# arduino_sh.net
KiCad netlist of a schematic drawn in Altium Designer
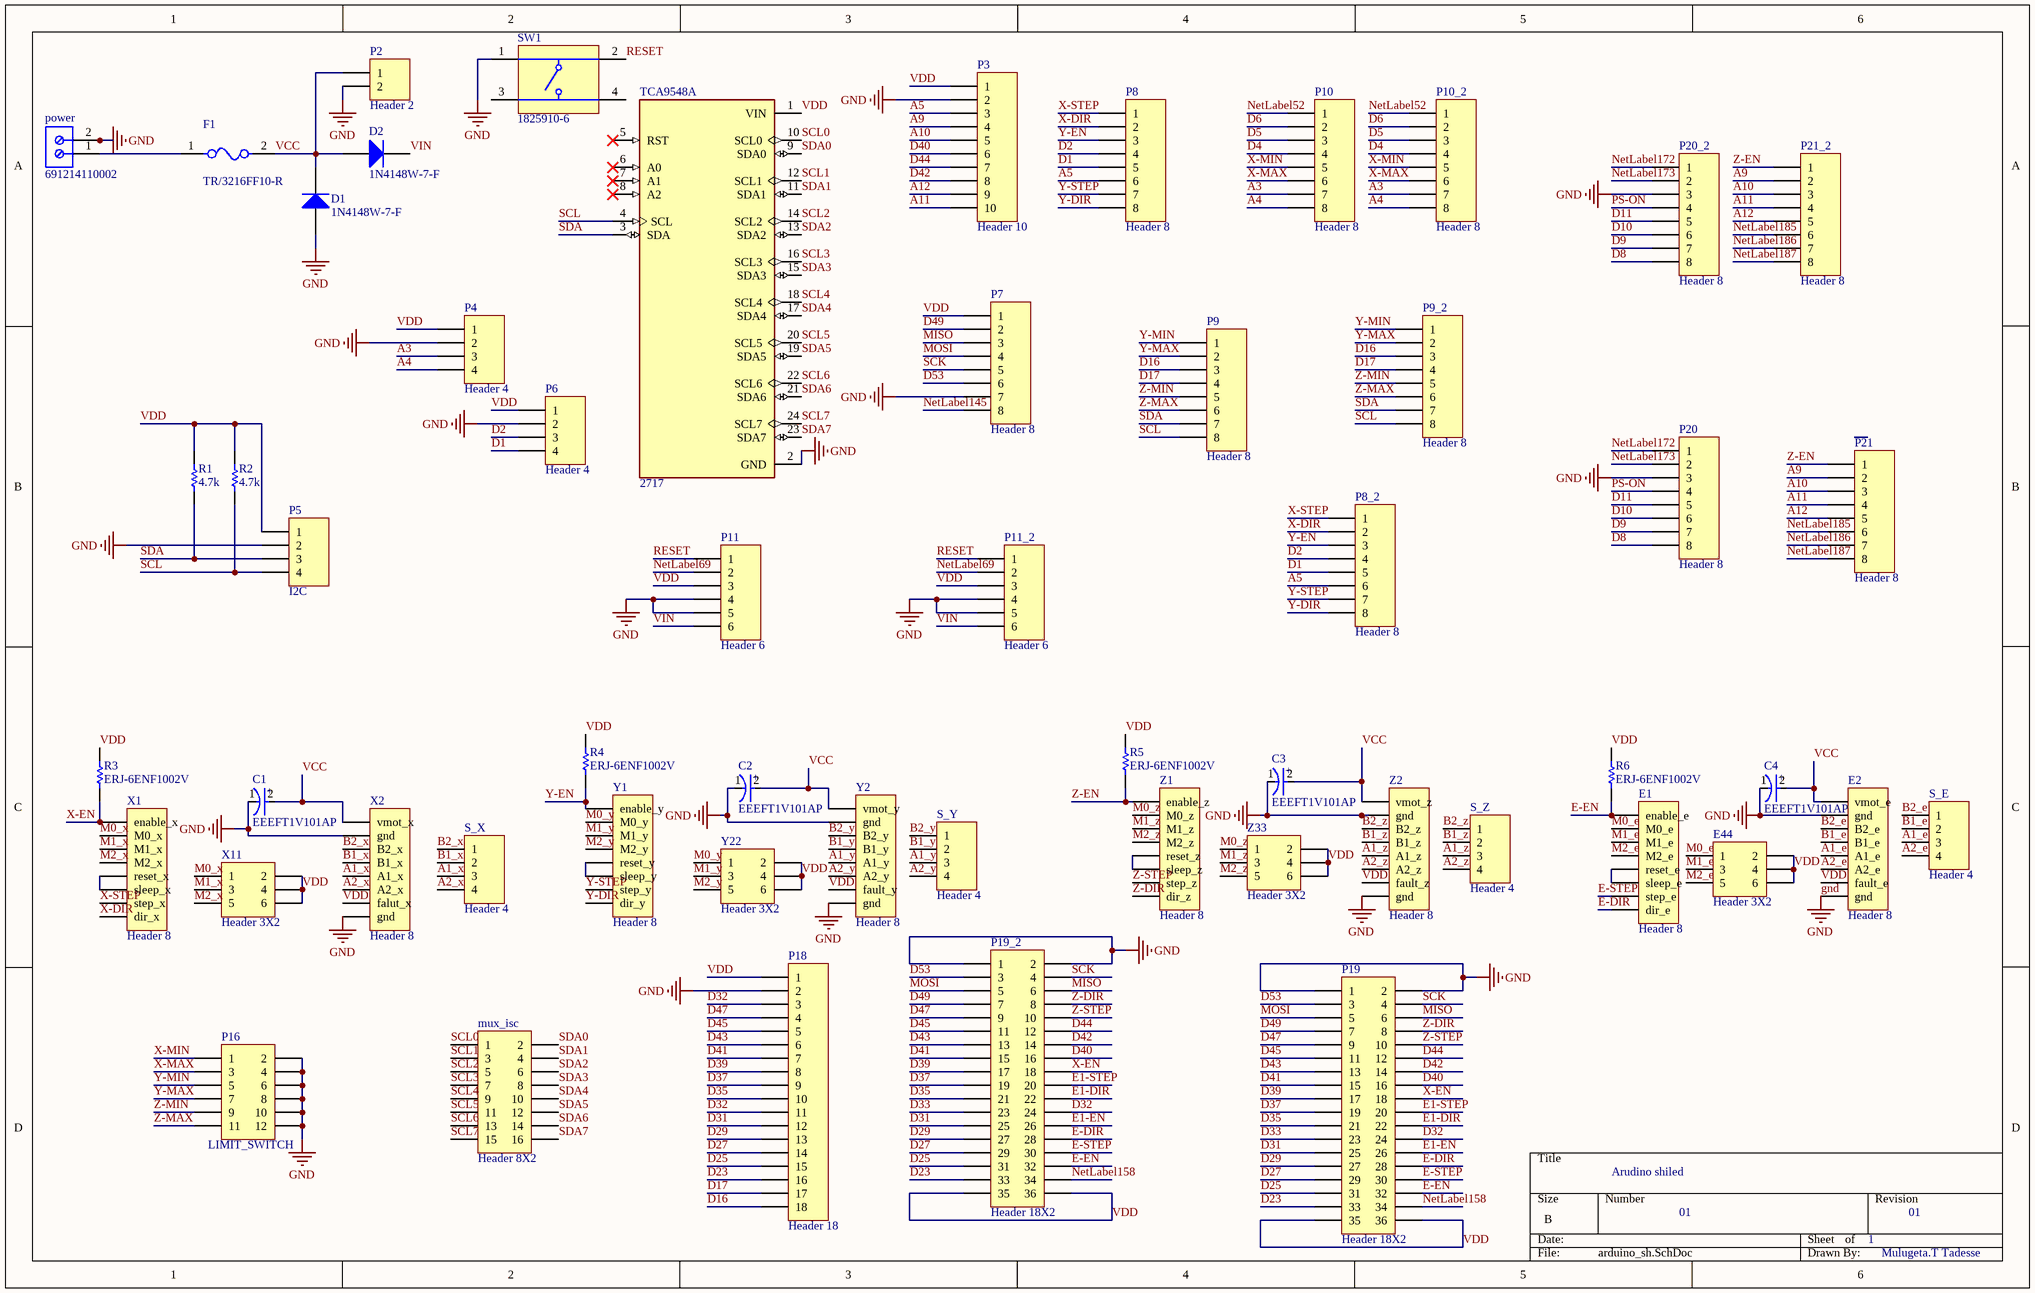
[diagram p0: arduino_sh.SchDoc]

(export (version "E")
  (design (tool "Eeschema 10.0.6"))
  (components
    (comp (ref "C1")
      (value "EEEFT1V101AP")
      (footprint "FP-FTD-MFG")
      (description "CAP ALUM 100UF 20% 35V SMD")
      (fields (field (name "VOLTAGE") "35V") (field (name "TOLERANCE") "20%"))
      (libsource (lib "Altium Content Vault") (part "a00bbbee19879c290e62620ae7e47b1"))
    )
    (comp (ref "C2")
      (value "EEEFT1V101AP")
      (footprint "FP-FTD-MFG")
      (description "CAP ALUM 100UF 20% 35V SMD")
      (fields (field (name "VOLTAGE") "35V") (field (name "TOLERANCE") "20%"))
      (libsource (lib "Altium Content Vault") (part "a00bbbee19879c290e62620ae7e47b1"))
    )
    (comp (ref "C3")
      (value "EEEFT1V101AP")
      (footprint "FP-FTD-MFG")
      (description "CAP ALUM 100UF 20% 35V SMD")
      (fields (field (name "VOLTAGE") "35V") (field (name "TOLERANCE") "20%"))
      (libsource (lib "Altium Content Vault") (part "a00bbbee19879c290e62620ae7e47b1"))
    )
    (comp (ref "C4")
      (value "EEEFT1V101AP")
      (footprint "FP-FTD-MFG")
      (description "CAP ALUM 100UF 20% 35V SMD")
      (fields (field (name "VOLTAGE") "35V") (field (name "TOLERANCE") "20%"))
      (libsource (lib "Altium Content Vault") (part "a00bbbee19879c290e62620ae7e47b1"))
    )
    (comp (ref "D1")
      (value "1N4148W-7-F")
      (footprint "DIOD-SOD123-2_V")
      (description "Fast Switching Diode, 100 V, 0.15 A, -65 to 150 degC, 2-Pin?SOD123, RoHS, Tape and Reel")
      (fields (field (name "MANUFACTURER") "DiodesIncorporated"))
      (libsource (lib "Altium Content Vault") (part "D-AK-2"))
    )
    (comp (ref "D2")
      (value "1N4148W-7-F")
      (footprint "DIOD-SOD123-2_V")
      (description "Fast Switching Diode, 100 V, 0.15 A, -65 to 150 degC, 2-Pin?SOD123, RoHS, Tape and Reel")
      (fields (field (name "MANUFACTURER") "DiodesIncorporated"))
      (libsource (lib "Altium Content Vault") (part "D-AK-2"))
    )
    (comp (ref "E1")
      (value "Header 8")
      (footprint "HDR1X8")
      (description "Header, 8-Pin")
      (fields (field (name "PUBLISHER") "Altium Limited"))
      (libsource (lib "Miscellaneous Connectors") (part "Header 8"))
    )
    (comp (ref "E2")
      (value "Header 8")
      (footprint "HDR1X8")
      (description "Header, 8-Pin")
      (fields (field (name "PUBLISHER") "Altium Limited"))
      (libsource (lib "Miscellaneous Connectors") (part "Header 8"))
    )
    (comp (ref "E44")
      (value "Header 3X2")
      (footprint "HDR2X3")
      (description "Header, 3-Pin, Dual row")
      (fields (field (name "PUBLISHER") "Altium Limited"))
      (libsource (lib "Miscellaneous Connectors") (part "Header 3X2"))
    )
    (comp (ref "F1")
      (value "TR/3216FF10-R")
      (footprint "FP-3216FF-MFG")
      (libsource (lib "Altium Content Vault") (part "5bcf9b9f640e542cf0359d10258e979"))
    )
    (comp (ref "mux_isc")
      (value "Header 8X2")
      (footprint "HDR2X8")
      (description "Header, 8-Pin, Dual row")
      (fields (field (name "PUBLISHER") "Altium Limited"))
      (libsource (lib "Miscellaneous Connectors") (part "Header 8X2"))
    )
    (comp (ref "P2")
      (value "Header 2")
      (footprint "HDR1X2")
      (description "Header, 2-Pin")
      (fields (field (name "PUBLISHER") "Altium Limited"))
      (libsource (lib "Miscellaneous Connectors") (part "Header 2"))
    )
    (comp (ref "P3")
      (value "Header 10")
      (footprint "HDR1X10")
      (description "Header, 10-Pin")
      (fields (field (name "PUBLISHER") "Altium Limited"))
      (libsource (lib "Miscellaneous Connectors") (part "Header 10"))
    )
    (comp (ref "P4")
      (value "Header 4")
      (footprint "HDR1X4")
      (description "Header, 4-Pin")
      (fields (field (name "PUBLISHER") "Altium Limited"))
      (libsource (lib "Miscellaneous Connectors") (part "Header 4"))
    )
    (comp (ref "P5")
      (value "I2C")
      (footprint "HDR1X4")
      (description "Header, 4-Pin")
      (fields (field (name "PUBLISHER") "Altium Limited"))
      (libsource (lib "Miscellaneous Connectors") (part "Header 4"))
    )
    (comp (ref "P6")
      (value "Header 4")
      (footprint "HDR1X4")
      (description "Header, 4-Pin")
      (fields (field (name "PUBLISHER") "Altium Limited"))
      (libsource (lib "Miscellaneous Connectors") (part "Header 4"))
    )
    (comp (ref "P7")
      (value "Header 8")
      (footprint "HDR1X8")
      (description "Header, 8-Pin")
      (fields (field (name "PUBLISHER") "Altium Limited"))
      (libsource (lib "Miscellaneous Connectors") (part "Header 8"))
    )
    (comp (ref "P8")
      (value "Header 8")
      (footprint "HDR1X8")
      (description "Header, 8-Pin")
      (fields (field (name "PUBLISHER") "Altium Limited"))
      (libsource (lib "Miscellaneous Connectors") (part "Header 8"))
    )
    (comp (ref "P8_2")
      (value "Header 8")
      (footprint "HDR1X8")
      (description "Header, 8-Pin")
      (fields (field (name "PUBLISHER") "Altium Limited"))
      (libsource (lib "Miscellaneous Connectors") (part "Header 8"))
    )
    (comp (ref "P9")
      (value "Header 8")
      (footprint "HDR1X8")
      (description "Header, 8-Pin")
      (fields (field (name "PUBLISHER") "Altium Limited"))
      (libsource (lib "Miscellaneous Connectors") (part "Header 8"))
    )
    (comp (ref "P9_2")
      (value "Header 8")
      (footprint "HDR1X8")
      (description "Header, 8-Pin")
      (fields (field (name "PUBLISHER") "Altium Limited"))
      (libsource (lib "Miscellaneous Connectors") (part "Header 8"))
    )
    (comp (ref "P10")
      (value "Header 8")
      (footprint "HDR1X8")
      (description "Header, 8-Pin")
      (fields (field (name "PUBLISHER") "Altium Limited"))
      (libsource (lib "Miscellaneous Connectors") (part "Header 8"))
    )
    (comp (ref "P10_2")
      (value "Header 8")
      (footprint "HDR1X8")
      (description "Header, 8-Pin")
      (fields (field (name "PUBLISHER") "Altium Limited"))
      (libsource (lib "Miscellaneous Connectors") (part "Header 8"))
    )
    (comp (ref "P11")
      (value "Header 6")
      (footprint "HDR1X6")
      (description "Header, 6-Pin")
      (fields (field (name "PUBLISHER") "Altium Limited"))
      (libsource (lib "Miscellaneous Connectors") (part "Header 6"))
    )
    (comp (ref "P11_2")
      (value "Header 6")
      (footprint "HDR1X6")
      (description "Header, 6-Pin")
      (fields (field (name "PUBLISHER") "Altium Limited"))
      (libsource (lib "Miscellaneous Connectors") (part "Header 6"))
    )
    (comp (ref "P16")
      (value "LIMIT_SWITCH")
      (footprint "HDR2X6")
      (description "Header, 6-Pin, Dual row")
      (fields (field (name "PUBLISHER") "Altium Limited"))
      (libsource (lib "Miscellaneous Connectors") (part "Header 6X2"))
    )
    (comp (ref "P18")
      (value "Header 18")
      (footprint "HDR1X18")
      (description "Header, 18-Pin")
      (fields (field (name "PUBLISHER") "Altium Limited"))
      (libsource (lib "Miscellaneous Connectors") (part "Header 18"))
    )
    (comp (ref "P19")
      (value "Header 18X2")
      (footprint "HDR2X18")
      (description "Header, 18-Pin, Dual row")
      (fields (field (name "PUBLISHER") "Altium Limited"))
      (libsource (lib "Miscellaneous Connectors") (part "Header 18X2"))
    )
    (comp (ref "P19_2")
      (value "Header 18X2")
      (footprint "HDR2X18")
      (description "Header, 18-Pin, Dual row")
      (fields (field (name "PUBLISHER") "Altium Limited"))
      (libsource (lib "Miscellaneous Connectors") (part "Header 18X2"))
    )
    (comp (ref "P20")
      (value "Header 8")
      (footprint "HDR1X8")
      (description "Header, 8-Pin")
      (fields (field (name "PUBLISHER") "Altium Limited"))
      (libsource (lib "Miscellaneous Connectors") (part "Header 8"))
    )
    (comp (ref "P20_2")
      (value "Header 8")
      (footprint "HDR1X8")
      (description "Header, 8-Pin")
      (fields (field (name "PUBLISHER") "Altium Limited"))
      (libsource (lib "Miscellaneous Connectors") (part "Header 8"))
    )
    (comp (ref "P21")
      (value "Header 8")
      (footprint "HDR1X8")
      (description "Header, 8-Pin")
      (fields (field (name "PUBLISHER") "Altium Limited"))
      (libsource (lib "Miscellaneous Connectors") (part "Header 8"))
    )
    (comp (ref "P21_2")
      (value "Header 8")
      (footprint "HDR1X8")
      (description "Header, 8-Pin")
      (fields (field (name "PUBLISHER") "Altium Limited"))
      (libsource (lib "Miscellaneous Connectors") (part "Header 8"))
    )
    (comp (ref "power")
      (value "691214110002")
      (footprint "691214110002")
      (fields (field (name "VOLTAGE") "300V"))
      (libsource (lib "Altium Content Vault") (part "TBL - 1R - 02P - Screw"))
    )
    (comp (ref "R1")
      (value "4.7k")
      (footprint "RESC2013X70X40ML20T20")
      (fields (field (name "MANUFACTURER") "Panasonic") (field (name "PART NUMBER") "ERJ-6ENF1002V"))
      (libsource (lib "Altium Content Vault") (part "RES"))
    )
    (comp (ref "R2")
      (value "4.7k")
      (footprint "RESC2013X70X40ML20T20")
      (fields (field (name "MANUFACTURER") "Panasonic") (field (name "PART NUMBER") "ERJ-6ENF1002V"))
      (libsource (lib "Altium Content Vault") (part "RES"))
    )
    (comp (ref "R3")
      (value "ERJ-6ENF1002V")
      (footprint "RESC2013X70X40ML20T20")
      (fields (field (name "MANUFACTURER") "Panasonic"))
      (libsource (lib "Altium Content Vault") (part "RES"))
    )
    (comp (ref "R4")
      (value "ERJ-6ENF1002V")
      (footprint "RESC2013X70X40ML20T20")
      (fields (field (name "MANUFACTURER") "Panasonic"))
      (libsource (lib "Altium Content Vault") (part "RES"))
    )
    (comp (ref "R5")
      (value "ERJ-6ENF1002V")
      (footprint "RESC2013X70X40ML20T20")
      (fields (field (name "MANUFACTURER") "Panasonic"))
      (libsource (lib "Altium Content Vault") (part "RES"))
    )
    (comp (ref "R6")
      (value "ERJ-6ENF1002V")
      (footprint "RESC2013X70X40ML20T20")
      (fields (field (name "MANUFACTURER") "Panasonic"))
      (libsource (lib "Altium Content Vault") (part "RES"))
    )
    (comp (ref "SW1")
      (value "1825910-6")
      (footprint "TECO-1825910-6_V")
      (description "Tact Switch, SPST-NO, 0.05 A, -35 to 85 degC, 4-Pin THD, RoHS, Bulk")
      (fields (field (name "MANUFACTURER") "TE Connectivity"))
      (libsource (lib "Altium Content Vault") (part "SW-SPST-4_A"))
    )
    (comp (ref "S_E")
      (value "Header 4")
      (footprint "HDR1X4")
      (description "Header, 4-Pin")
      (fields (field (name "PUBLISHER") "Altium Limited"))
      (libsource (lib "Miscellaneous Connectors") (part "Header 4"))
    )
    (comp (ref "S_X")
      (value "Header 4")
      (footprint "HDR1X4")
      (description "Header, 4-Pin")
      (fields (field (name "PUBLISHER") "Altium Limited"))
      (libsource (lib "Miscellaneous Connectors") (part "Header 4"))
    )
    (comp (ref "S_Y")
      (value "Header 4")
      (footprint "HDR1X4")
      (description "Header, 4-Pin")
      (fields (field (name "PUBLISHER") "Altium Limited"))
      (libsource (lib "Miscellaneous Connectors") (part "Header 4"))
    )
    (comp (ref "S_Z")
      (value "Header 4")
      (footprint "HDR1X4")
      (description "Header, 4-Pin")
      (fields (field (name "PUBLISHER") "Altium Limited"))
      (libsource (lib "Miscellaneous Connectors") (part "Header 4"))
    )
    (comp (ref "TCA9548A")
      (value "2717")
      (footprint "MODULE_2717")
      (description "Module: multiplexer; I2C interface multiplexer; TCA9548A; 3Ã·5VDC")
      (fields (field (name "MF") "Adafruit"))
      (libsource (lib "2717") (part "2717"))
    )
    (comp (ref "X1")
      (value "Header 8")
      (footprint "HDR1X8")
      (description "Header, 8-Pin")
      (fields (field (name "PUBLISHER") "Altium Limited"))
      (libsource (lib "Miscellaneous Connectors") (part "Header 8"))
    )
    (comp (ref "X2")
      (value "Header 8")
      (footprint "HDR1X8")
      (description "Header, 8-Pin")
      (fields (field (name "PUBLISHER") "Altium Limited"))
      (libsource (lib "Miscellaneous Connectors") (part "Header 8"))
    )
    (comp (ref "X11")
      (value "Header 3X2")
      (footprint "HDR2X3")
      (description "Header, 3-Pin, Dual row")
      (fields (field (name "PUBLISHER") "Altium Limited"))
      (libsource (lib "Miscellaneous Connectors") (part "Header 3X2"))
    )
    (comp (ref "Y1")
      (value "Header 8")
      (footprint "HDR1X8")
      (description "Header, 8-Pin")
      (fields (field (name "PUBLISHER") "Altium Limited"))
      (libsource (lib "Miscellaneous Connectors") (part "Header 8"))
    )
    (comp (ref "Y2")
      (value "Header 8")
      (footprint "HDR1X8")
      (description "Header, 8-Pin")
      (fields (field (name "PUBLISHER") "Altium Limited"))
      (libsource (lib "Miscellaneous Connectors") (part "Header 8"))
    )
    (comp (ref "Y22")
      (value "Header 3X2")
      (footprint "HDR2X3")
      (description "Header, 3-Pin, Dual row")
      (fields (field (name "PUBLISHER") "Altium Limited"))
      (libsource (lib "Miscellaneous Connectors") (part "Header 3X2"))
    )
    (comp (ref "Z1")
      (value "Header 8")
      (footprint "HDR1X8")
      (description "Header, 8-Pin")
      (fields (field (name "PUBLISHER") "Altium Limited"))
      (libsource (lib "Miscellaneous Connectors") (part "Header 8"))
    )
    (comp (ref "Z2")
      (value "Header 8")
      (footprint "HDR1X8")
      (description "Header, 8-Pin")
      (fields (field (name "PUBLISHER") "Altium Limited"))
      (libsource (lib "Miscellaneous Connectors") (part "Header 8"))
    )
    (comp (ref "Z33")
      (value "Header 3X2")
      (footprint "HDR2X3")
      (description "Header, 3-Pin, Dual row")
      (fields (field (name "PUBLISHER") "Altium Limited"))
      (libsource (lib "Miscellaneous Connectors") (part "Header 3X2"))
    )
  )
  (nets
    (net (code "1") (name "/A1_e") (class "Default")
      (node (ref "E2") (pin "5") (pinfunction "5_5") (pintype "passive"))
      (node (ref "S_E") (pin "3") (pinfunction "3_3") (pintype "passive"))
    )
    (net (code "2") (name "/A1_x") (class "Default")
      (node (ref "S_X") (pin "3") (pinfunction "3_3") (pintype "passive"))
      (node (ref "X2") (pin "5") (pinfunction "5_5") (pintype "passive"))
    )
    (net (code "3") (name "/A1_y") (class "Default")
      (node (ref "S_Y") (pin "3") (pinfunction "3_3") (pintype "passive"))
      (node (ref "Y2") (pin "5") (pinfunction "5_5") (pintype "passive"))
    )
    (net (code "4") (name "/A1_z") (class "Default")
      (node (ref "S_Z") (pin "3") (pinfunction "3_3") (pintype "passive"))
      (node (ref "Z2") (pin "5") (pinfunction "5_5") (pintype "passive"))
    )
    (net (code "5") (name "/A2_e") (class "Default")
      (node (ref "E2") (pin "6") (pinfunction "6_6") (pintype "passive"))
      (node (ref "S_E") (pin "4") (pinfunction "4_4") (pintype "passive"))
    )
    (net (code "6") (name "/A2_x") (class "Default")
      (node (ref "S_X") (pin "4") (pinfunction "4_4") (pintype "passive"))
      (node (ref "X2") (pin "6") (pinfunction "6_6") (pintype "passive"))
    )
    (net (code "7") (name "/A2_y") (class "Default")
      (node (ref "S_Y") (pin "4") (pinfunction "4_4") (pintype "passive"))
      (node (ref "Y2") (pin "6") (pinfunction "6_6") (pintype "passive"))
    )
    (net (code "8") (name "/A2_z") (class "Default")
      (node (ref "S_Z") (pin "4") (pinfunction "4_4") (pintype "passive"))
      (node (ref "Z2") (pin "6") (pinfunction "6_6") (pintype "passive"))
    )
    (net (code "9") (name "/A3") (class "Default")
      (node (ref "P10") (pin "7") (pinfunction "7_7") (pintype "passive"))
      (node (ref "P10_2") (pin "7") (pinfunction "7_7") (pintype "passive"))
      (node (ref "P4") (pin "3") (pinfunction "3_3") (pintype "passive"))
    )
    (net (code "10") (name "/A4") (class "Default")
      (node (ref "P10") (pin "8") (pinfunction "8_8") (pintype "passive"))
      (node (ref "P10_2") (pin "8") (pinfunction "8_8") (pintype "passive"))
      (node (ref "P4") (pin "4") (pinfunction "4_4") (pintype "passive"))
    )
    (net (code "11") (name "/A5") (class "Default")
      (node (ref "P3") (pin "3") (pinfunction "3_3") (pintype "passive"))
      (node (ref "P8") (pin "6") (pinfunction "6_6") (pintype "passive"))
      (node (ref "P8_2") (pin "6") (pinfunction "6_6") (pintype "passive"))
    )
    (net (code "12") (name "/A9") (class "Default")
      (node (ref "P21") (pin "2") (pinfunction "2_2") (pintype "passive"))
      (node (ref "P21_2") (pin "2") (pinfunction "2_2") (pintype "passive"))
      (node (ref "P3") (pin "4") (pinfunction "4_4") (pintype "passive"))
    )
    (net (code "13") (name "/A10") (class "Default")
      (node (ref "P21") (pin "3") (pinfunction "3_3") (pintype "passive"))
      (node (ref "P21_2") (pin "3") (pinfunction "3_3") (pintype "passive"))
      (node (ref "P3") (pin "5") (pinfunction "5_5") (pintype "passive"))
    )
    (net (code "14") (name "/A11") (class "Default")
      (node (ref "P21") (pin "4") (pinfunction "4_4") (pintype "passive"))
      (node (ref "P21_2") (pin "4") (pinfunction "4_4") (pintype "passive"))
      (node (ref "P3") (pin "10") (pinfunction "10_10") (pintype "passive"))
    )
    (net (code "15") (name "/A12") (class "Default")
      (node (ref "P21") (pin "5") (pinfunction "5_5") (pintype "passive"))
      (node (ref "P21_2") (pin "5") (pinfunction "5_5") (pintype "passive"))
      (node (ref "P3") (pin "9") (pinfunction "9_9") (pintype "passive"))
    )
    (net (code "16") (name "/B1_e") (class "Default")
      (node (ref "E2") (pin "4") (pinfunction "4_4") (pintype "passive"))
      (node (ref "S_E") (pin "2") (pinfunction "2_2") (pintype "passive"))
    )
    (net (code "17") (name "/B1_x") (class "Default")
      (node (ref "S_X") (pin "2") (pinfunction "2_2") (pintype "passive"))
      (node (ref "X2") (pin "4") (pinfunction "4_4") (pintype "passive"))
    )
    (net (code "18") (name "/B1_y") (class "Default")
      (node (ref "S_Y") (pin "2") (pinfunction "2_2") (pintype "passive"))
      (node (ref "Y2") (pin "4") (pinfunction "4_4") (pintype "passive"))
    )
    (net (code "19") (name "/B1_z") (class "Default")
      (node (ref "S_Z") (pin "2") (pinfunction "2_2") (pintype "passive"))
      (node (ref "Z2") (pin "4") (pinfunction "4_4") (pintype "passive"))
    )
    (net (code "20") (name "/B2_e") (class "Default")
      (node (ref "E2") (pin "3") (pinfunction "3_3") (pintype "passive"))
      (node (ref "S_E") (pin "1") (pinfunction "1_1") (pintype "passive"))
    )
    (net (code "21") (name "/B2_x") (class "Default")
      (node (ref "S_X") (pin "1") (pinfunction "1_1") (pintype "passive"))
      (node (ref "X2") (pin "3") (pinfunction "3_3") (pintype "passive"))
    )
    (net (code "22") (name "/B2_y") (class "Default")
      (node (ref "S_Y") (pin "1") (pinfunction "1_1") (pintype "passive"))
      (node (ref "Y2") (pin "3") (pinfunction "3_3") (pintype "passive"))
    )
    (net (code "23") (name "/B2_z") (class "Default")
      (node (ref "S_Z") (pin "1") (pinfunction "1_1") (pintype "passive"))
      (node (ref "Z2") (pin "3") (pinfunction "3_3") (pintype "passive"))
    )
    (net (code "24") (name "/D1") (class "Default")
      (node (ref "P6") (pin "4") (pinfunction "4_4") (pintype "passive"))
      (node (ref "P8") (pin "5") (pinfunction "5_5") (pintype "passive"))
      (node (ref "P8_2") (pin "5") (pinfunction "5_5") (pintype "passive"))
    )
    (net (code "25") (name "/D2") (class "Default")
      (node (ref "P6") (pin "3") (pinfunction "3_3") (pintype "passive"))
      (node (ref "P8") (pin "4") (pinfunction "4_4") (pintype "passive"))
      (node (ref "P8_2") (pin "4") (pinfunction "4_4") (pintype "passive"))
    )
    (net (code "26") (name "/D4") (class "Default")
      (node (ref "P10") (pin "4") (pinfunction "4_4") (pintype "passive"))
      (node (ref "P10_2") (pin "4") (pinfunction "4_4") (pintype "passive"))
    )
    (net (code "27") (name "/D5") (class "Default")
      (node (ref "P10") (pin "3") (pinfunction "3_3") (pintype "passive"))
      (node (ref "P10_2") (pin "3") (pinfunction "3_3") (pintype "passive"))
    )
    (net (code "28") (name "/D6") (class "Default")
      (node (ref "P10") (pin "2") (pinfunction "2_2") (pintype "passive"))
      (node (ref "P10_2") (pin "2") (pinfunction "2_2") (pintype "passive"))
    )
    (net (code "29") (name "/D8") (class "Default")
      (node (ref "P20") (pin "8") (pinfunction "8_8") (pintype "passive"))
      (node (ref "P20_2") (pin "8") (pinfunction "8_8") (pintype "passive"))
    )
    (net (code "30") (name "/D9") (class "Default")
      (node (ref "P20") (pin "7") (pinfunction "7_7") (pintype "passive"))
      (node (ref "P20_2") (pin "7") (pinfunction "7_7") (pintype "passive"))
    )
    (net (code "31") (name "/D10") (class "Default")
      (node (ref "P20") (pin "6") (pinfunction "6_6") (pintype "passive"))
      (node (ref "P20_2") (pin "6") (pinfunction "6_6") (pintype "passive"))
    )
    (net (code "32") (name "/D11") (class "Default")
      (node (ref "P20") (pin "5") (pinfunction "5_5") (pintype "passive"))
      (node (ref "P20_2") (pin "5") (pinfunction "5_5") (pintype "passive"))
    )
    (net (code "33") (name "/D16") (class "Default")
      (node (ref "P18") (pin "18") (pinfunction "18_18") (pintype "passive"))
      (node (ref "P9") (pin "3") (pinfunction "3_3") (pintype "passive"))
      (node (ref "P9_2") (pin "3") (pinfunction "3_3") (pintype "passive"))
    )
    (net (code "34") (name "/D17") (class "Default")
      (node (ref "P18") (pin "17") (pinfunction "17_17") (pintype "passive"))
      (node (ref "P9") (pin "4") (pinfunction "4_4") (pintype "passive"))
      (node (ref "P9_2") (pin "4") (pinfunction "4_4") (pintype "passive"))
    )
    (net (code "35") (name "/D23") (class "Default")
      (node (ref "P18") (pin "16") (pinfunction "16_16") (pintype "passive"))
      (node (ref "P19") (pin "33") (pinfunction "33_33") (pintype "passive"))
      (node (ref "P19_2") (pin "33") (pinfunction "33_33") (pintype "passive"))
    )
    (net (code "36") (name "/D25") (class "Default")
      (node (ref "P18") (pin "15") (pinfunction "15_15") (pintype "passive"))
      (node (ref "P19") (pin "31") (pinfunction "31_31") (pintype "passive"))
      (node (ref "P19_2") (pin "31") (pinfunction "31_31") (pintype "passive"))
    )
    (net (code "37") (name "/D27") (class "Default")
      (node (ref "P18") (pin "14") (pinfunction "14_14") (pintype "passive"))
      (node (ref "P19") (pin "29") (pinfunction "29_29") (pintype "passive"))
      (node (ref "P19_2") (pin "29") (pinfunction "29_29") (pintype "passive"))
    )
    (net (code "38") (name "/D29") (class "Default")
      (node (ref "P18") (pin "13") (pinfunction "13_13") (pintype "passive"))
      (node (ref "P19") (pin "27") (pinfunction "27_27") (pintype "passive"))
      (node (ref "P19_2") (pin "27") (pinfunction "27_27") (pintype "passive"))
    )
    (net (code "39") (name "/D31") (class "Default")
      (node (ref "P18") (pin "12") (pinfunction "12_12") (pintype "passive"))
      (node (ref "P19") (pin "25") (pinfunction "25_25") (pintype "passive"))
      (node (ref "P19_2") (pin "25") (pinfunction "25_25") (pintype "passive"))
    )
    (net (code "40") (name "/D32") (class "Default")
      (node (ref "P18") (pin "11") (pinfunction "11_11") (pintype "passive"))
      (node (ref "P18") (pin "3") (pinfunction "3_3") (pintype "passive"))
      (node (ref "P19") (pin "24") (pinfunction "24_24") (pintype "passive"))
      (node (ref "P19_2") (pin "24") (pinfunction "24_24") (pintype "passive"))
    )
    (net (code "41") (name "/D33") (class "Default")
      (node (ref "P19") (pin "23") (pinfunction "23_23") (pintype "passive"))
      (node (ref "P19_2") (pin "23") (pinfunction "23_23") (pintype "passive"))
    )
    (net (code "42") (name "/D35") (class "Default")
      (node (ref "P18") (pin "10") (pinfunction "10_10") (pintype "passive"))
      (node (ref "P19") (pin "21") (pinfunction "21_21") (pintype "passive"))
      (node (ref "P19_2") (pin "21") (pinfunction "21_21") (pintype "passive"))
    )
    (net (code "43") (name "/D37") (class "Default")
      (node (ref "P18") (pin "9") (pinfunction "9_9") (pintype "passive"))
      (node (ref "P19") (pin "19") (pinfunction "19_19") (pintype "passive"))
      (node (ref "P19_2") (pin "19") (pinfunction "19_19") (pintype "passive"))
    )
    (net (code "44") (name "/D39") (class "Default")
      (node (ref "P18") (pin "8") (pinfunction "8_8") (pintype "passive"))
      (node (ref "P19") (pin "17") (pinfunction "17_17") (pintype "passive"))
      (node (ref "P19_2") (pin "17") (pinfunction "17_17") (pintype "passive"))
    )
    (net (code "45") (name "/D40") (class "Default")
      (node (ref "P19") (pin "16") (pinfunction "16_16") (pintype "passive"))
      (node (ref "P19_2") (pin "16") (pinfunction "16_16") (pintype "passive"))
      (node (ref "P3") (pin "6") (pinfunction "6_6") (pintype "passive"))
    )
    (net (code "46") (name "/D41") (class "Default")
      (node (ref "P18") (pin "7") (pinfunction "7_7") (pintype "passive"))
      (node (ref "P19") (pin "15") (pinfunction "15_15") (pintype "passive"))
      (node (ref "P19_2") (pin "15") (pinfunction "15_15") (pintype "passive"))
    )
    (net (code "47") (name "/D42") (class "Default")
      (node (ref "P19") (pin "14") (pinfunction "14_14") (pintype "passive"))
      (node (ref "P19_2") (pin "14") (pinfunction "14_14") (pintype "passive"))
      (node (ref "P3") (pin "8") (pinfunction "8_8") (pintype "passive"))
    )
    (net (code "48") (name "/D43") (class "Default")
      (node (ref "P18") (pin "6") (pinfunction "6_6") (pintype "passive"))
      (node (ref "P19") (pin "13") (pinfunction "13_13") (pintype "passive"))
      (node (ref "P19_2") (pin "13") (pinfunction "13_13") (pintype "passive"))
    )
    (net (code "49") (name "/D44") (class "Default")
      (node (ref "P19") (pin "12") (pinfunction "12_12") (pintype "passive"))
      (node (ref "P19_2") (pin "12") (pinfunction "12_12") (pintype "passive"))
      (node (ref "P3") (pin "7") (pinfunction "7_7") (pintype "passive"))
    )
    (net (code "50") (name "/D45") (class "Default")
      (node (ref "P18") (pin "5") (pinfunction "5_5") (pintype "passive"))
      (node (ref "P19") (pin "11") (pinfunction "11_11") (pintype "passive"))
      (node (ref "P19_2") (pin "11") (pinfunction "11_11") (pintype "passive"))
    )
    (net (code "51") (name "/D47") (class "Default")
      (node (ref "P18") (pin "4") (pinfunction "4_4") (pintype "passive"))
      (node (ref "P19") (pin "9") (pinfunction "9_9") (pintype "passive"))
      (node (ref "P19_2") (pin "9") (pinfunction "9_9") (pintype "passive"))
    )
    (net (code "52") (name "/D49") (class "Default")
      (node (ref "P19") (pin "7") (pinfunction "7_7") (pintype "passive"))
      (node (ref "P19_2") (pin "7") (pinfunction "7_7") (pintype "passive"))
      (node (ref "P7") (pin "2") (pinfunction "2_2") (pintype "passive"))
    )
    (net (code "53") (name "/D53") (class "Default")
      (node (ref "P19") (pin "3") (pinfunction "3_3") (pintype "passive"))
      (node (ref "P19_2") (pin "3") (pinfunction "3_3") (pintype "passive"))
      (node (ref "P7") (pin "6") (pinfunction "6_6") (pintype "passive"))
    )
    (net (code "54") (name "/E-DIR") (class "Default")
      (node (ref "E1") (pin "8") (pinfunction "8_8") (pintype "passive"))
      (node (ref "P19") (pin "28") (pinfunction "28_28") (pintype "passive"))
      (node (ref "P19_2") (pin "28") (pinfunction "28_28") (pintype "passive"))
    )
    (net (code "55") (name "/E-EN") (class "Default")
      (node (ref "E1") (pin "1") (pinfunction "1_1") (pintype "passive"))
      (node (ref "P19") (pin "32") (pinfunction "32_32") (pintype "passive"))
      (node (ref "P19_2") (pin "32") (pinfunction "32_32") (pintype "passive"))
      (node (ref "R6") (pin "2") (pinfunction "2_2") (pintype "passive"))
    )
    (net (code "56") (name "/E-STEP") (class "Default")
      (node (ref "E1") (pin "7") (pinfunction "7_7") (pintype "passive"))
      (node (ref "P19") (pin "30") (pinfunction "30_30") (pintype "passive"))
      (node (ref "P19_2") (pin "30") (pinfunction "30_30") (pintype "passive"))
    )
    (net (code "57") (name "/E1-DIR") (class "Default")
      (node (ref "P19") (pin "22") (pinfunction "22_22") (pintype "passive"))
      (node (ref "P19_2") (pin "22") (pinfunction "22_22") (pintype "passive"))
    )
    (net (code "58") (name "/E1-EN") (class "Default")
      (node (ref "P19") (pin "26") (pinfunction "26_26") (pintype "passive"))
      (node (ref "P19_2") (pin "26") (pinfunction "26_26") (pintype "passive"))
    )
    (net (code "59") (name "/E1-STEP") (class "Default")
      (node (ref "P19") (pin "20") (pinfunction "20_20") (pintype "passive"))
      (node (ref "P19_2") (pin "20") (pinfunction "20_20") (pintype "passive"))
    )
    (net (code "60") (name "/M0_e") (class "Default")
      (node (ref "E1") (pin "2") (pinfunction "2_2") (pintype "passive"))
      (node (ref "E44") (pin "1") (pinfunction "1_1") (pintype "passive"))
    )
    (net (code "61") (name "/M0_x") (class "Default")
      (node (ref "X1") (pin "2") (pinfunction "2_2") (pintype "passive"))
      (node (ref "X11") (pin "1") (pinfunction "1_1") (pintype "passive"))
    )
    (net (code "62") (name "/M0_y") (class "Default")
      (node (ref "Y1") (pin "2") (pinfunction "2_2") (pintype "passive"))
      (node (ref "Y22") (pin "1") (pinfunction "1_1") (pintype "passive"))
    )
    (net (code "63") (name "/M0_z") (class "Default")
      (node (ref "Z1") (pin "2") (pinfunction "2_2") (pintype "passive"))
      (node (ref "Z33") (pin "1") (pinfunction "1_1") (pintype "passive"))
    )
    (net (code "64") (name "/M1_e") (class "Default")
      (node (ref "E1") (pin "3") (pinfunction "3_3") (pintype "passive"))
      (node (ref "E44") (pin "3") (pinfunction "3_3") (pintype "passive"))
    )
    (net (code "65") (name "/M1_x") (class "Default")
      (node (ref "X1") (pin "3") (pinfunction "3_3") (pintype "passive"))
      (node (ref "X11") (pin "3") (pinfunction "3_3") (pintype "passive"))
    )
    (net (code "66") (name "/M1_y") (class "Default")
      (node (ref "Y1") (pin "3") (pinfunction "3_3") (pintype "passive"))
      (node (ref "Y22") (pin "3") (pinfunction "3_3") (pintype "passive"))
    )
    (net (code "67") (name "/M1_z") (class "Default")
      (node (ref "Z1") (pin "3") (pinfunction "3_3") (pintype "passive"))
      (node (ref "Z33") (pin "3") (pinfunction "3_3") (pintype "passive"))
    )
    (net (code "68") (name "/M2_e") (class "Default")
      (node (ref "E1") (pin "4") (pinfunction "4_4") (pintype "passive"))
      (node (ref "E44") (pin "5") (pinfunction "5_5") (pintype "passive"))
    )
    (net (code "69") (name "/M2_x") (class "Default")
      (node (ref "X1") (pin "4") (pinfunction "4_4") (pintype "passive"))
      (node (ref "X11") (pin "5") (pinfunction "5_5") (pintype "passive"))
    )
    (net (code "70") (name "/M2_y") (class "Default")
      (node (ref "Y1") (pin "4") (pinfunction "4_4") (pintype "passive"))
      (node (ref "Y22") (pin "5") (pinfunction "5_5") (pintype "passive"))
    )
    (net (code "71") (name "/M2_z") (class "Default")
      (node (ref "Z1") (pin "4") (pinfunction "4_4") (pintype "passive"))
      (node (ref "Z33") (pin "5") (pinfunction "5_5") (pintype "passive"))
    )
    (net (code "72") (name "/MISO") (class "Default")
      (node (ref "P19") (pin "6") (pinfunction "6_6") (pintype "passive"))
      (node (ref "P19_2") (pin "6") (pinfunction "6_6") (pintype "passive"))
      (node (ref "P7") (pin "3") (pinfunction "3_3") (pintype "passive"))
    )
    (net (code "73") (name "/MOSI") (class "Default")
      (node (ref "P19") (pin "5") (pinfunction "5_5") (pintype "passive"))
      (node (ref "P19_2") (pin "5") (pinfunction "5_5") (pintype "passive"))
      (node (ref "P7") (pin "4") (pinfunction "4_4") (pintype "passive"))
    )
    (net (code "74") (name "/NetLabel52") (class "Default")
      (node (ref "P10") (pin "1") (pinfunction "1_1") (pintype "passive"))
      (node (ref "P10_2") (pin "1") (pinfunction "1_1") (pintype "passive"))
    )
    (net (code "75") (name "/NetLabel69") (class "Default")
      (node (ref "P11") (pin "2") (pinfunction "2_2") (pintype "passive"))
      (node (ref "P11_2") (pin "2") (pinfunction "2_2") (pintype "passive"))
    )
    (net (code "76") (name "/NetLabel145") (class "Default")
      (node (ref "P7") (pin "8") (pinfunction "8_8") (pintype "passive"))
    )
    (net (code "77") (name "/NetLabel158") (class "Default")
      (node (ref "P19") (pin "34") (pinfunction "34_34") (pintype "passive"))
      (node (ref "P19_2") (pin "34") (pinfunction "34_34") (pintype "passive"))
    )
    (net (code "78") (name "/NetLabel172") (class "Default")
      (node (ref "P20") (pin "1") (pinfunction "1_1") (pintype "passive"))
      (node (ref "P20_2") (pin "1") (pinfunction "1_1") (pintype "passive"))
    )
    (net (code "79") (name "/NetLabel173") (class "Default")
      (node (ref "P20") (pin "2") (pinfunction "2_2") (pintype "passive"))
      (node (ref "P20_2") (pin "2") (pinfunction "2_2") (pintype "passive"))
    )
    (net (code "80") (name "/NetLabel185") (class "Default")
      (node (ref "P21") (pin "6") (pinfunction "6_6") (pintype "passive"))
      (node (ref "P21_2") (pin "6") (pinfunction "6_6") (pintype "passive"))
    )
    (net (code "81") (name "/NetLabel186") (class "Default")
      (node (ref "P21") (pin "7") (pinfunction "7_7") (pintype "passive"))
      (node (ref "P21_2") (pin "7") (pinfunction "7_7") (pintype "passive"))
    )
    (net (code "82") (name "/NetLabel187") (class "Default")
      (node (ref "P21") (pin "8") (pinfunction "8_8") (pintype "passive"))
      (node (ref "P21_2") (pin "8") (pinfunction "8_8") (pintype "passive"))
    )
    (net (code "83") (name "/PS-ON") (class "Default")
      (node (ref "P20") (pin "4") (pinfunction "4_4") (pintype "passive"))
      (node (ref "P20_2") (pin "4") (pinfunction "4_4") (pintype "passive"))
    )
    (net (code "84") (name "/RESET") (class "Default")
      (node (ref "P11") (pin "1") (pinfunction "1_1") (pintype "passive"))
      (node (ref "P11_2") (pin "1") (pinfunction "1_1") (pintype "passive"))
      (node (ref "SW1") (pin "2") (pinfunction "2_2") (pintype "passive"))
    )
    (net (code "85") (name "/SCK") (class "Default")
      (node (ref "P19") (pin "4") (pinfunction "4_4") (pintype "passive"))
      (node (ref "P19_2") (pin "4") (pinfunction "4_4") (pintype "passive"))
      (node (ref "P7") (pin "5") (pinfunction "5_5") (pintype "passive"))
    )
    (net (code "86") (name "/SCL") (class "Default")
      (node (ref "P5") (pin "4") (pinfunction "4_4") (pintype "passive"))
      (node (ref "P9") (pin "8") (pinfunction "8_8") (pintype "passive"))
      (node (ref "P9_2") (pin "8") (pinfunction "8_8") (pintype "passive"))
      (node (ref "R2") (pin "2") (pinfunction "2_2") (pintype "passive"))
      (node (ref "TCA9548A") (pin "4") (pinfunction "SCL_4") (pintype "input"))
    )
    (net (code "87") (name "/SCL0") (class "Default")
      (node (ref "TCA9548A") (pin "10") (pinfunction "SCL0_10") (pintype "output"))
      (node (ref "mux_isc") (pin "1") (pinfunction "1_1") (pintype "passive"))
    )
    (net (code "88") (name "/SCL1") (class "Default")
      (node (ref "TCA9548A") (pin "12") (pinfunction "SCL1_12") (pintype "output"))
      (node (ref "mux_isc") (pin "3") (pinfunction "3_3") (pintype "passive"))
    )
    (net (code "89") (name "/SCL2") (class "Default")
      (node (ref "TCA9548A") (pin "14") (pinfunction "SCL2_14") (pintype "output"))
      (node (ref "mux_isc") (pin "5") (pinfunction "5_5") (pintype "passive"))
    )
    (net (code "90") (name "/SCL3") (class "Default")
      (node (ref "TCA9548A") (pin "16") (pinfunction "SCL3_16") (pintype "output"))
      (node (ref "mux_isc") (pin "7") (pinfunction "7_7") (pintype "passive"))
    )
    (net (code "91") (name "/SCL4") (class "Default")
      (node (ref "TCA9548A") (pin "18") (pinfunction "SCL4_18") (pintype "output"))
      (node (ref "mux_isc") (pin "9") (pinfunction "9_9") (pintype "passive"))
    )
    (net (code "92") (name "/SCL5") (class "Default")
      (node (ref "TCA9548A") (pin "20") (pinfunction "SCL5_20") (pintype "output"))
      (node (ref "mux_isc") (pin "11") (pinfunction "11_11") (pintype "passive"))
    )
    (net (code "93") (name "/SCL6") (class "Default")
      (node (ref "TCA9548A") (pin "22") (pinfunction "SCL6_22") (pintype "output"))
      (node (ref "mux_isc") (pin "13") (pinfunction "13_13") (pintype "passive"))
    )
    (net (code "94") (name "/SCL7") (class "Default")
      (node (ref "TCA9548A") (pin "24") (pinfunction "SCL7_24") (pintype "output"))
      (node (ref "mux_isc") (pin "15") (pinfunction "15_15") (pintype "passive"))
    )
    (net (code "95") (name "/SDA") (class "Default")
      (node (ref "P5") (pin "3") (pinfunction "3_3") (pintype "passive"))
      (node (ref "P9") (pin "7") (pinfunction "7_7") (pintype "passive"))
      (node (ref "P9_2") (pin "7") (pinfunction "7_7") (pintype "passive"))
      (node (ref "R1") (pin "2") (pinfunction "2_2") (pintype "passive"))
      (node (ref "TCA9548A") (pin "3") (pinfunction "SDA_3") (pintype "bidirectional"))
    )
    (net (code "96") (name "/SDA0") (class "Default")
      (node (ref "TCA9548A") (pin "9") (pinfunction "SDA0_9") (pintype "bidirectional"))
      (node (ref "mux_isc") (pin "2") (pinfunction "2_2") (pintype "passive"))
    )
    (net (code "97") (name "/SDA1") (class "Default")
      (node (ref "TCA9548A") (pin "11") (pinfunction "SDA1_11") (pintype "bidirectional"))
      (node (ref "mux_isc") (pin "4") (pinfunction "4_4") (pintype "passive"))
    )
    (net (code "98") (name "/SDA2") (class "Default")
      (node (ref "TCA9548A") (pin "13") (pinfunction "SDA2_13") (pintype "bidirectional"))
      (node (ref "mux_isc") (pin "6") (pinfunction "6_6") (pintype "passive"))
    )
    (net (code "99") (name "/SDA3") (class "Default")
      (node (ref "TCA9548A") (pin "15") (pinfunction "SDA3_15") (pintype "bidirectional"))
      (node (ref "mux_isc") (pin "8") (pinfunction "8_8") (pintype "passive"))
    )
    (net (code "100") (name "/SDA4") (class "Default")
      (node (ref "TCA9548A") (pin "17") (pinfunction "SDA4_17") (pintype "bidirectional"))
      (node (ref "mux_isc") (pin "10") (pinfunction "10_10") (pintype "passive"))
    )
    (net (code "101") (name "/SDA5") (class "Default")
      (node (ref "TCA9548A") (pin "19") (pinfunction "SDA5_19") (pintype "bidirectional"))
      (node (ref "mux_isc") (pin "12") (pinfunction "12_12") (pintype "passive"))
    )
    (net (code "102") (name "/SDA6") (class "Default")
      (node (ref "TCA9548A") (pin "21") (pinfunction "SDA6_21") (pintype "bidirectional"))
      (node (ref "mux_isc") (pin "14") (pinfunction "14_14") (pintype "passive"))
    )
    (net (code "103") (name "/SDA7") (class "Default")
      (node (ref "TCA9548A") (pin "23") (pinfunction "SDA7_23") (pintype "bidirectional"))
      (node (ref "mux_isc") (pin "16") (pinfunction "16_16") (pintype "passive"))
    )
    (net (code "104") (name "/VCC") (class "Default")
      (node (ref "C1") (pin "2") (pinfunction "A_2") (pintype "passive"))
      (node (ref "C2") (pin "2") (pinfunction "A_2") (pintype "passive"))
      (node (ref "C3") (pin "2") (pinfunction "A_2") (pintype "passive"))
      (node (ref "C4") (pin "2") (pinfunction "A_2") (pintype "passive"))
      (node (ref "D1") (pin "2") (pinfunction "K_2") (pintype "passive"))
      (node (ref "D2") (pin "1") (pinfunction "A_1") (pintype "passive"))
      (node (ref "E2") (pin "1") (pinfunction "1_1") (pintype "passive"))
      (node (ref "F1") (pin "2") (pinfunction "2_2") (pintype "passive"))
      (node (ref "P2") (pin "1") (pinfunction "1_1") (pintype "passive"))
      (node (ref "X2") (pin "1") (pinfunction "1_1") (pintype "passive"))
      (node (ref "Y2") (pin "1") (pinfunction "1_1") (pintype "passive"))
      (node (ref "Z2") (pin "1") (pinfunction "1_1") (pintype "passive"))
    )
    (net (code "105") (name "/VDD") (class "Default")
      (node (ref "E2") (pin "7") (pinfunction "7_7") (pintype "passive"))
      (node (ref "E44") (pin "2") (pinfunction "2_2") (pintype "passive"))
      (node (ref "E44") (pin "4") (pinfunction "4_4") (pintype "passive"))
      (node (ref "E44") (pin "6") (pinfunction "6_6") (pintype "passive"))
      (node (ref "P11") (pin "3") (pinfunction "3_3") (pintype "passive"))
      (node (ref "P11_2") (pin "3") (pinfunction "3_3") (pintype "passive"))
      (node (ref "P18") (pin "1") (pinfunction "1_1") (pintype "passive"))
      (node (ref "P19") (pin "35") (pinfunction "35_35") (pintype "passive"))
      (node (ref "P19") (pin "36") (pinfunction "36_36") (pintype "passive"))
      (node (ref "P19_2") (pin "35") (pinfunction "35_35") (pintype "passive"))
      (node (ref "P19_2") (pin "36") (pinfunction "36_36") (pintype "passive"))
      (node (ref "P3") (pin "1") (pinfunction "1_1") (pintype "passive"))
      (node (ref "P4") (pin "1") (pinfunction "1_1") (pintype "passive"))
      (node (ref "P5") (pin "1") (pinfunction "1_1") (pintype "passive"))
      (node (ref "P6") (pin "1") (pinfunction "1_1") (pintype "passive"))
      (node (ref "P7") (pin "1") (pinfunction "1_1") (pintype "passive"))
      (node (ref "R1") (pin "1") (pinfunction "1_1") (pintype "passive"))
      (node (ref "R2") (pin "1") (pinfunction "1_1") (pintype "passive"))
      (node (ref "R3") (pin "1") (pinfunction "1_1") (pintype "passive"))
      (node (ref "R4") (pin "1") (pinfunction "1_1") (pintype "passive"))
      (node (ref "R5") (pin "1") (pinfunction "1_1") (pintype "passive"))
      (node (ref "R6") (pin "1") (pinfunction "1_1") (pintype "passive"))
      (node (ref "TCA9548A") (pin "1") (pinfunction "VIN_1") (pintype "power_in"))
      (node (ref "X11") (pin "2") (pinfunction "2_2") (pintype "passive"))
      (node (ref "X11") (pin "4") (pinfunction "4_4") (pintype "passive"))
      (node (ref "X11") (pin "6") (pinfunction "6_6") (pintype "passive"))
      (node (ref "X2") (pin "7") (pinfunction "7_7") (pintype "passive"))
      (node (ref "Y2") (pin "7") (pinfunction "7_7") (pintype "passive"))
      (node (ref "Y22") (pin "2") (pinfunction "2_2") (pintype "passive"))
      (node (ref "Y22") (pin "4") (pinfunction "4_4") (pintype "passive"))
      (node (ref "Y22") (pin "6") (pinfunction "6_6") (pintype "passive"))
      (node (ref "Z2") (pin "7") (pinfunction "7_7") (pintype "passive"))
      (node (ref "Z33") (pin "2") (pinfunction "2_2") (pintype "passive"))
      (node (ref "Z33") (pin "4") (pinfunction "4_4") (pintype "passive"))
      (node (ref "Z33") (pin "6") (pinfunction "6_6") (pintype "passive"))
    )
    (net (code "106") (name "/VIN") (class "Default")
      (node (ref "D2") (pin "2") (pinfunction "K_2") (pintype "passive"))
      (node (ref "P11") (pin "6") (pinfunction "6_6") (pintype "passive"))
      (node (ref "P11_2") (pin "6") (pinfunction "6_6") (pintype "passive"))
    )
    (net (code "107") (name "/X-DIR") (class "Default")
      (node (ref "P8") (pin "2") (pinfunction "2_2") (pintype "passive"))
      (node (ref "P8_2") (pin "2") (pinfunction "2_2") (pintype "passive"))
      (node (ref "X1") (pin "8") (pinfunction "8_8") (pintype "passive"))
    )
    (net (code "108") (name "/X-EN") (class "Default")
      (node (ref "P19") (pin "18") (pinfunction "18_18") (pintype "passive"))
      (node (ref "P19_2") (pin "18") (pinfunction "18_18") (pintype "passive"))
      (node (ref "R3") (pin "2") (pinfunction "2_2") (pintype "passive"))
      (node (ref "X1") (pin "1") (pinfunction "1_1") (pintype "passive"))
    )
    (net (code "109") (name "/X-MAX") (class "Default")
      (node (ref "P10") (pin "6") (pinfunction "6_6") (pintype "passive"))
      (node (ref "P10_2") (pin "6") (pinfunction "6_6") (pintype "passive"))
      (node (ref "P16") (pin "3") (pinfunction "3_3") (pintype "passive"))
    )
    (net (code "110") (name "/X-MIN") (class "Default")
      (node (ref "P10") (pin "5") (pinfunction "5_5") (pintype "passive"))
      (node (ref "P10_2") (pin "5") (pinfunction "5_5") (pintype "passive"))
      (node (ref "P16") (pin "1") (pinfunction "1_1") (pintype "passive"))
    )
    (net (code "111") (name "/X-STEP") (class "Default")
      (node (ref "P8") (pin "1") (pinfunction "1_1") (pintype "passive"))
      (node (ref "P8_2") (pin "1") (pinfunction "1_1") (pintype "passive"))
      (node (ref "X1") (pin "7") (pinfunction "7_7") (pintype "passive"))
    )
    (net (code "112") (name "/Y-DIR") (class "Default")
      (node (ref "P8") (pin "8") (pinfunction "8_8") (pintype "passive"))
      (node (ref "P8_2") (pin "8") (pinfunction "8_8") (pintype "passive"))
      (node (ref "Y1") (pin "8") (pinfunction "8_8") (pintype "passive"))
    )
    (net (code "113") (name "/Y-EN") (class "Default")
      (node (ref "P8") (pin "3") (pinfunction "3_3") (pintype "passive"))
      (node (ref "P8_2") (pin "3") (pinfunction "3_3") (pintype "passive"))
      (node (ref "R4") (pin "2") (pinfunction "2_2") (pintype "passive"))
      (node (ref "Y1") (pin "1") (pinfunction "1_1") (pintype "passive"))
    )
    (net (code "114") (name "/Y-MAX") (class "Default")
      (node (ref "P16") (pin "7") (pinfunction "7_7") (pintype "passive"))
      (node (ref "P9") (pin "2") (pinfunction "2_2") (pintype "passive"))
      (node (ref "P9_2") (pin "2") (pinfunction "2_2") (pintype "passive"))
    )
    (net (code "115") (name "/Y-MIN") (class "Default")
      (node (ref "P16") (pin "5") (pinfunction "5_5") (pintype "passive"))
      (node (ref "P9") (pin "1") (pinfunction "1_1") (pintype "passive"))
      (node (ref "P9_2") (pin "1") (pinfunction "1_1") (pintype "passive"))
    )
    (net (code "116") (name "/Y-STEP") (class "Default")
      (node (ref "P8") (pin "7") (pinfunction "7_7") (pintype "passive"))
      (node (ref "P8_2") (pin "7") (pinfunction "7_7") (pintype "passive"))
      (node (ref "Y1") (pin "7") (pinfunction "7_7") (pintype "passive"))
    )
    (net (code "117") (name "/Z-DIR") (class "Default")
      (node (ref "P19") (pin "8") (pinfunction "8_8") (pintype "passive"))
      (node (ref "P19_2") (pin "8") (pinfunction "8_8") (pintype "passive"))
      (node (ref "Z1") (pin "8") (pinfunction "8_8") (pintype "passive"))
    )
    (net (code "118") (name "/Z-EN") (class "Default")
      (node (ref "P21") (pin "1") (pinfunction "1_1") (pintype "passive"))
      (node (ref "P21_2") (pin "1") (pinfunction "1_1") (pintype "passive"))
      (node (ref "R5") (pin "2") (pinfunction "2_2") (pintype "passive"))
      (node (ref "Z1") (pin "1") (pinfunction "1_1") (pintype "passive"))
    )
    (net (code "119") (name "/Z-MAX") (class "Default")
      (node (ref "P16") (pin "11") (pinfunction "11_11") (pintype "passive"))
      (node (ref "P9") (pin "6") (pinfunction "6_6") (pintype "passive"))
      (node (ref "P9_2") (pin "6") (pinfunction "6_6") (pintype "passive"))
    )
    (net (code "120") (name "/Z-MIN") (class "Default")
      (node (ref "P16") (pin "9") (pinfunction "9_9") (pintype "passive"))
      (node (ref "P9") (pin "5") (pinfunction "5_5") (pintype "passive"))
      (node (ref "P9_2") (pin "5") (pinfunction "5_5") (pintype "passive"))
    )
    (net (code "121") (name "/Z-STEP") (class "Default")
      (node (ref "P19") (pin "10") (pinfunction "10_10") (pintype "passive"))
      (node (ref "P19_2") (pin "10") (pinfunction "10_10") (pintype "passive"))
      (node (ref "Z1") (pin "7") (pinfunction "7_7") (pintype "passive"))
    )
    (net (code "122") (name "GND") (class "Default")
      (node (ref "C1") (pin "1") (pinfunction "C_1") (pintype "passive"))
      (node (ref "C2") (pin "1") (pinfunction "C_1") (pintype "passive"))
      (node (ref "C3") (pin "1") (pinfunction "C_1") (pintype "passive"))
      (node (ref "C4") (pin "1") (pinfunction "C_1") (pintype "passive"))
      (node (ref "D1") (pin "1") (pinfunction "A_1") (pintype "passive"))
      (node (ref "E2") (pin "2") (pinfunction "2_2") (pintype "passive"))
      (node (ref "E2") (pin "8") (pinfunction "8_8") (pintype "passive"))
      (node (ref "P11") (pin "4") (pinfunction "4_4") (pintype "passive"))
      (node (ref "P11") (pin "5") (pinfunction "5_5") (pintype "passive"))
      (node (ref "P11_2") (pin "4") (pinfunction "4_4") (pintype "passive"))
      (node (ref "P11_2") (pin "5") (pinfunction "5_5") (pintype "passive"))
      (node (ref "P16") (pin "10") (pinfunction "10_10") (pintype "passive"))
      (node (ref "P16") (pin "12") (pinfunction "12_12") (pintype "passive"))
      (node (ref "P16") (pin "2") (pinfunction "2_2") (pintype "passive"))
      (node (ref "P16") (pin "4") (pinfunction "4_4") (pintype "passive"))
      (node (ref "P16") (pin "6") (pinfunction "6_6") (pintype "passive"))
      (node (ref "P16") (pin "8") (pinfunction "8_8") (pintype "passive"))
      (node (ref "P18") (pin "2") (pinfunction "2_2") (pintype "passive"))
      (node (ref "P19") (pin "1") (pinfunction "1_1") (pintype "passive"))
      (node (ref "P19") (pin "2") (pinfunction "2_2") (pintype "passive"))
      (node (ref "P19_2") (pin "1") (pinfunction "1_1") (pintype "passive"))
      (node (ref "P19_2") (pin "2") (pinfunction "2_2") (pintype "passive"))
      (node (ref "P2") (pin "2") (pinfunction "2_2") (pintype "passive"))
      (node (ref "P20") (pin "3") (pinfunction "3_3") (pintype "passive"))
      (node (ref "P20_2") (pin "3") (pinfunction "3_3") (pintype "passive"))
      (node (ref "P3") (pin "2") (pinfunction "2_2") (pintype "passive"))
      (node (ref "P4") (pin "2") (pinfunction "2_2") (pintype "passive"))
      (node (ref "P5") (pin "2") (pinfunction "2_2") (pintype "passive"))
      (node (ref "P6") (pin "2") (pinfunction "2_2") (pintype "passive"))
      (node (ref "P7") (pin "7") (pinfunction "7_7") (pintype "passive"))
      (node (ref "SW1") (pin "1") (pinfunction "1_1") (pintype "passive"))
      (node (ref "TCA9548A") (pin "2") (pinfunction "GND_2") (pintype "power_in"))
      (node (ref "X2") (pin "2") (pinfunction "2_2") (pintype "passive"))
      (node (ref "X2") (pin "8") (pinfunction "8_8") (pintype "passive"))
      (node (ref "Y2") (pin "2") (pinfunction "2_2") (pintype "passive"))
      (node (ref "Y2") (pin "8") (pinfunction "8_8") (pintype "passive"))
      (node (ref "Z2") (pin "2") (pinfunction "2_2") (pintype "passive"))
      (node (ref "Z2") (pin "8") (pinfunction "8_8") (pintype "passive"))
      (node (ref "power") (pin "2") (pinfunction "2_2") (pintype "passive"))
    )
    (net (code "123") (name "Net-(E1-Pad5)") (class "Default")
      (node (ref "E1") (pin "5") (pinfunction "5_5") (pintype "passive"))
      (node (ref "E1") (pin "6") (pinfunction "6_6") (pintype "passive"))
    )
    (net (code "124") (name "Net-(F1-Pad1)") (class "Default")
      (node (ref "F1") (pin "1") (pinfunction "1_1") (pintype "passive"))
      (node (ref "power") (pin "1") (pinfunction "1_1") (pintype "passive"))
    )
    (net (code "125") (name "Net-(X1-Pad5)") (class "Default")
      (node (ref "X1") (pin "5") (pinfunction "5_5") (pintype "passive"))
      (node (ref "X1") (pin "6") (pinfunction "6_6") (pintype "passive"))
    )
    (net (code "126") (name "Net-(Y1-Pad5)") (class "Default")
      (node (ref "Y1") (pin "5") (pinfunction "5_5") (pintype "passive"))
      (node (ref "Y1") (pin "6") (pinfunction "6_6") (pintype "passive"))
    )
    (net (code "127") (name "Net-(Z1-Pad5)") (class "Default")
      (node (ref "Z1") (pin "5") (pinfunction "5_5") (pintype "passive"))
      (node (ref "Z1") (pin "6") (pinfunction "6_6") (pintype "passive"))
    )
    (net (code "128") (name "unconnected-(SW1-Pad3)") (class "Default")
      (node (ref "SW1") (pin "3") (pinfunction "3_3") (pintype "passive"))
    )
    (net (code "129") (name "unconnected-(SW1-Pad4)") (class "Default")
      (node (ref "SW1") (pin "4") (pinfunction "4_4") (pintype "passive"))
    )
    (net (code "130") (name "unconnected-(TCA9548A-A0-Pad6)") (class "Default")
      (node (ref "TCA9548A") (pin "6") (pinfunction "A0_6") (pintype "input+no_connect"))
    )
    (net (code "131") (name "unconnected-(TCA9548A-A1-Pad7)") (class "Default")
      (node (ref "TCA9548A") (pin "7") (pinfunction "A1_7") (pintype "input+no_connect"))
    )
    (net (code "132") (name "unconnected-(TCA9548A-A2-Pad8)") (class "Default")
      (node (ref "TCA9548A") (pin "8") (pinfunction "A2_8") (pintype "input+no_connect"))
    )
    (net (code "133") (name "unconnected-(TCA9548A-RST-Pad5)") (class "Default")
      (node (ref "TCA9548A") (pin "5") (pinfunction "RST_5") (pintype "input+no_connect"))
    )
  )
)
